# CTRL.net
KiCad netlist of a schematic drawn in Altium Designer
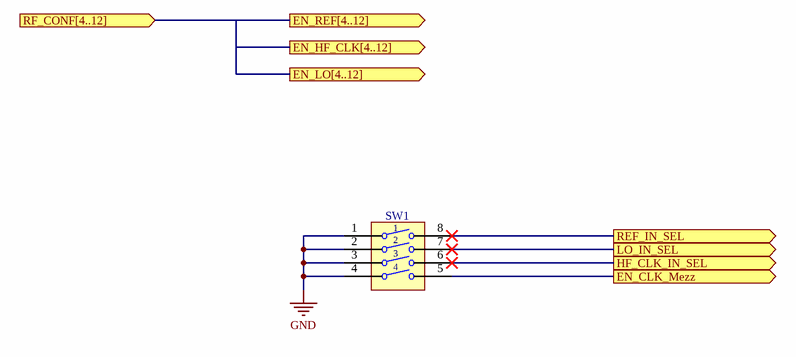
[diagram p0: CTRL.SchDoc]

(export (version "E")
  (design (tool "Eeschema 10.0.6"))
  (components
    (comp (ref "SW1")
      (value "Switch")
      (footprint "SW_CTS_219-4MST")
      (description "4 Ways SPST DIP Switch")
      (fields
        (field (name "PART NUMBER") "SW_CTS_219-4MST")
        (field (name "MANUFACTURER") "CTS ELECTROCOMPONENTS")
        (field (name "AUTHOR") "CERN DEM JLC")
      )
      (libsource (lib "Eletro-mechanical") (part "SW 4x SPST DIP Switch"))
    )
  )
  (nets
    (net (code "10") (name "/EN_CLK_Mezz") (class "Default")
      (node (ref "SW1") (pin "5") (pinfunction "5_5") (pintype "passive"))
    )
    (net (code "12") (name "/HF_CLK_IN_SEL") (class "Default")
      (node (ref "SW1") (pin "6") (pinfunction "6_6") (pintype "passive+no_connect"))
    )
    (net (code "13") (name "/LO_IN_SEL") (class "Default")
      (node (ref "SW1") (pin "7") (pinfunction "7_7") (pintype "passive+no_connect"))
    )
    (net (code "14") (name "/REF_IN_SEL") (class "Default")
      (node (ref "SW1") (pin "8") (pinfunction "8_8") (pintype "passive+no_connect"))
    )
    (net (code "15") (name "GND") (class "Default")
      (node (ref "SW1") (pin "1") (pinfunction "1_1") (pintype "passive"))
      (node (ref "SW1") (pin "2") (pinfunction "2_2") (pintype "passive"))
      (node (ref "SW1") (pin "3") (pinfunction "3_3") (pintype "passive"))
      (node (ref "SW1") (pin "4") (pinfunction "4_4") (pintype "passive"))
    )
  )
)
